# ADA4817.net
KiCad netlist of a schematic drawn in Altium Designer
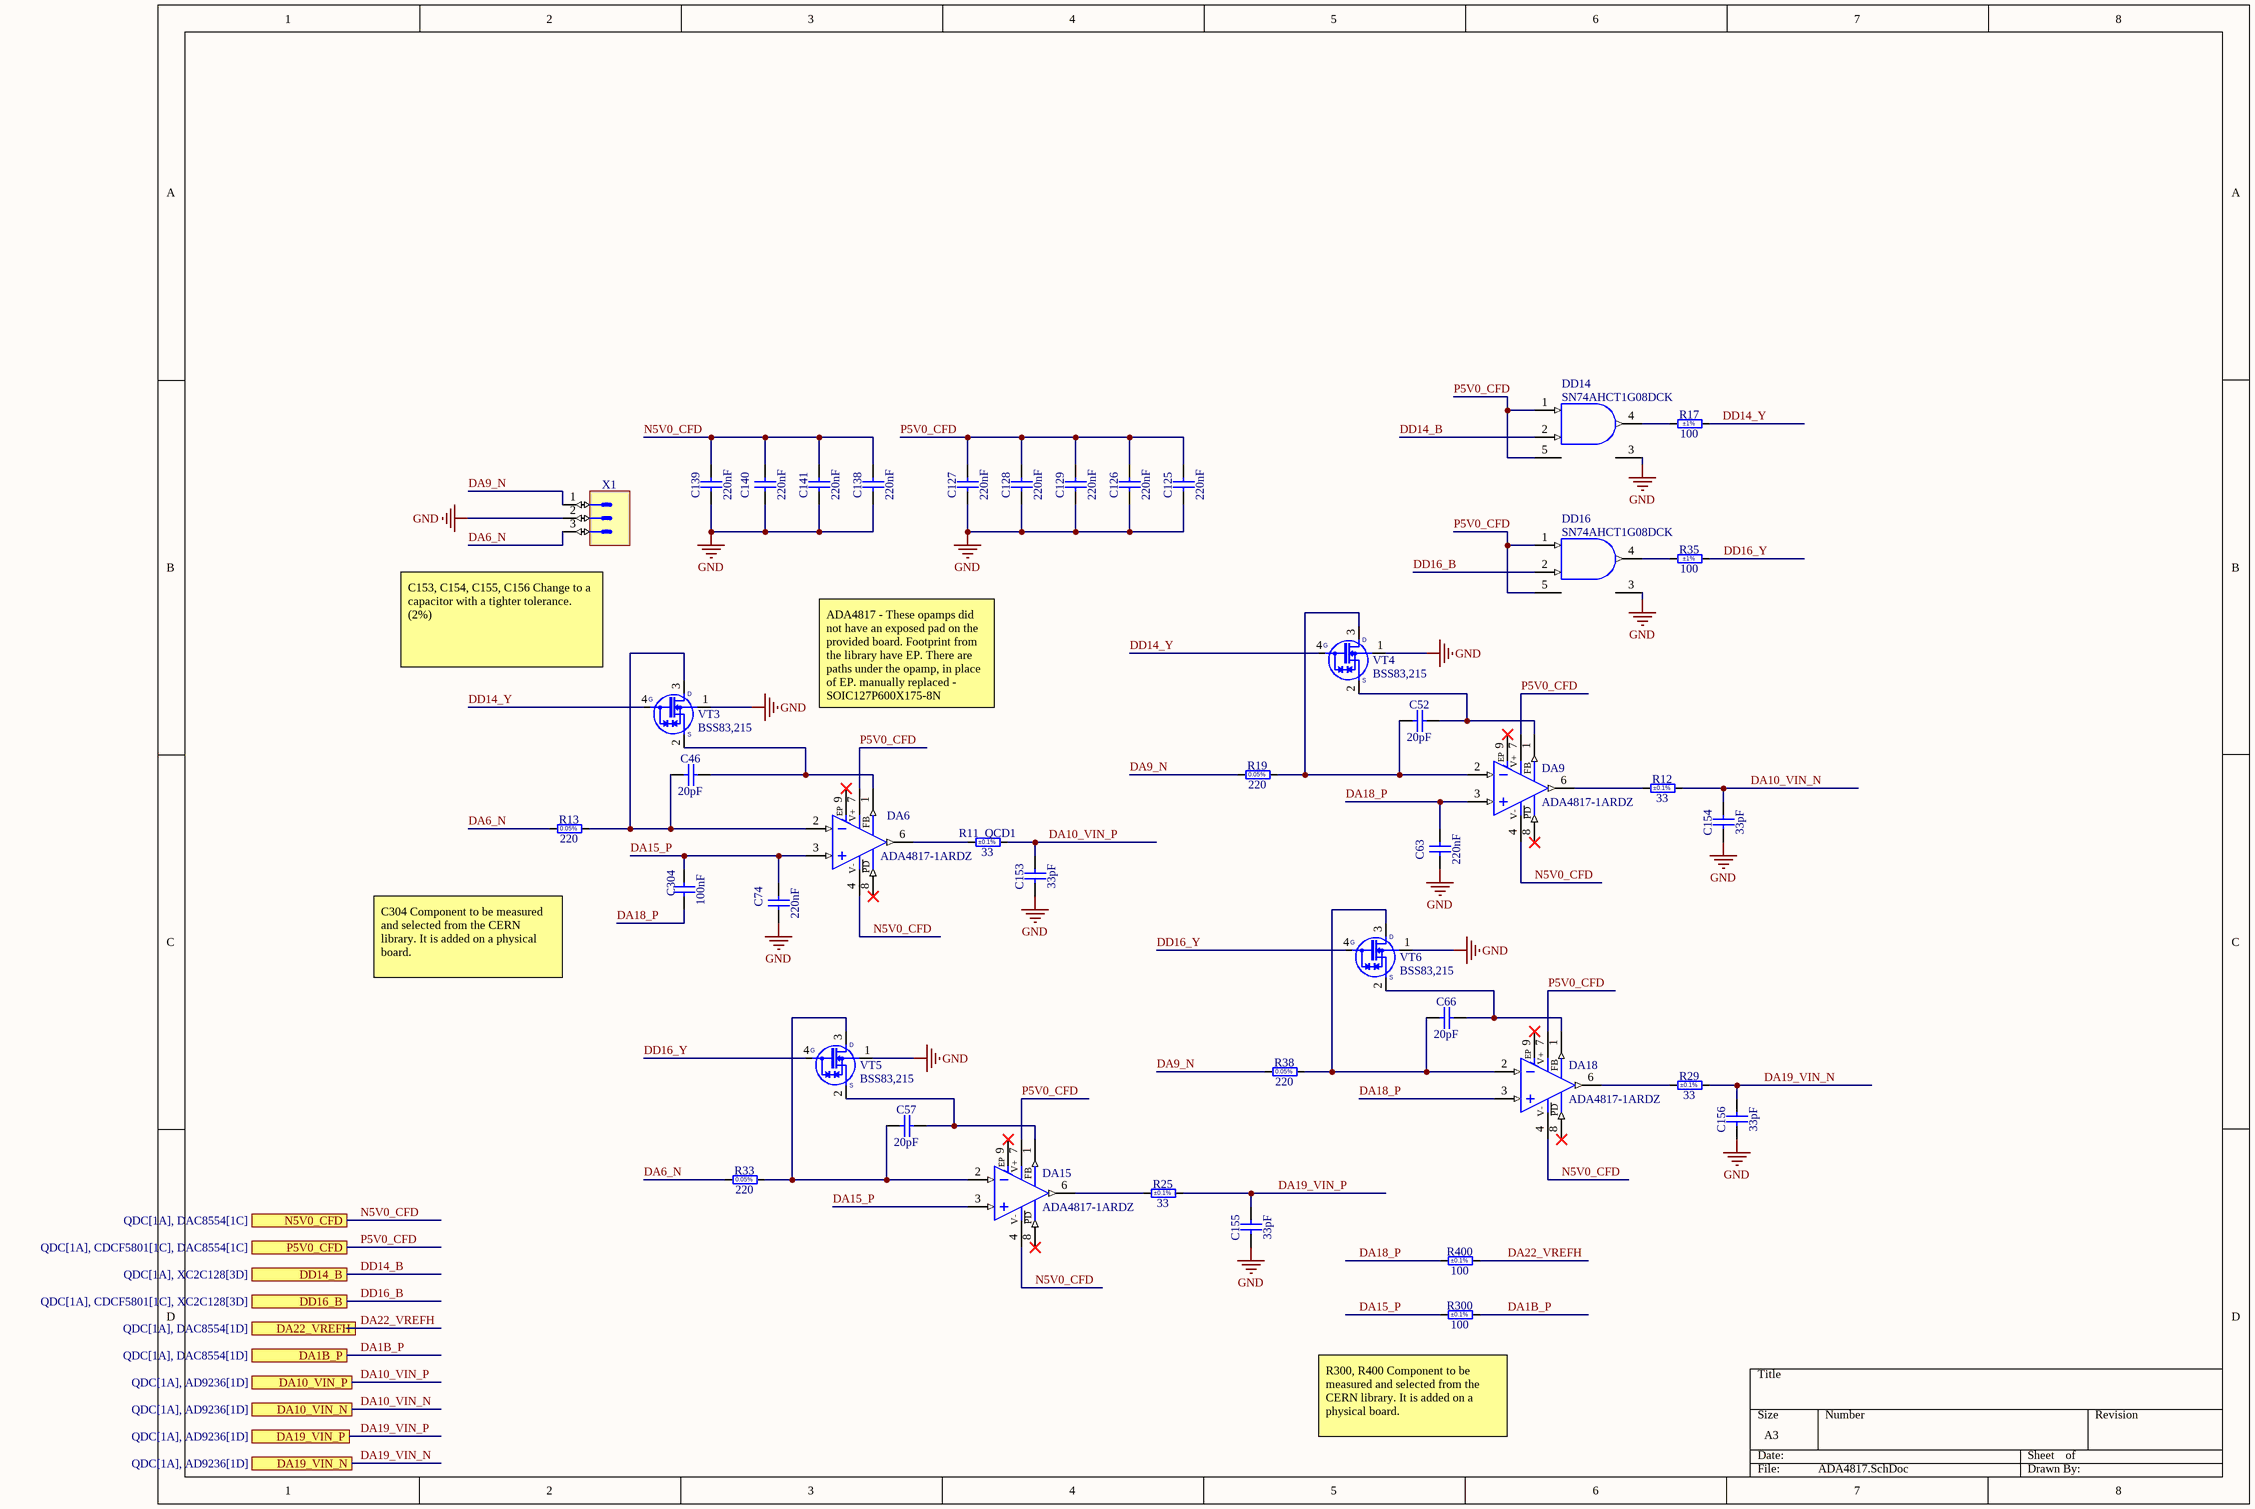
[diagram p0: ADA4817.SchDoc]

(export (version "E")
  (design (tool "Eeschema 10.0.6"))
  (components
    (comp (ref "C46")
      (value "20pF")
      (footprint "CAPC2012X135N")
      (description "Non-polarised capacitor")
      (fields
        (field (name "PART NUMBER") "CC0805_20PF_50V_2%_C0G")
        (field (name "VOLTAGE") "50V")
        (field (name "AUTHOR") "CERN DEM HF")
      )
      (libsource (lib "Capacitors") (part "Capacitor - non polarized"))
    )
    (comp (ref "C52")
      (value "20pF")
      (footprint "CAPC2012X135N")
      (description "Non-polarised capacitor")
      (fields
        (field (name "PART NUMBER") "CC0805_20PF_50V_2%_C0G")
        (field (name "VOLTAGE") "50V")
        (field (name "AUTHOR") "CERN DEM HF")
      )
      (libsource (lib "Capacitors") (part "Capacitor - non polarized"))
    )
    (comp (ref "C57")
      (value "20pF")
      (footprint "CAPC2012X135N")
      (description "Non-polarised capacitor")
      (fields
        (field (name "PART NUMBER") "CC0805_20PF_50V_2%_C0G")
        (field (name "VOLTAGE") "50V")
        (field (name "AUTHOR") "CERN DEM HF")
      )
      (libsource (lib "Capacitors") (part "Capacitor - non polarized"))
    )
    (comp (ref "C63")
      (value "220nF")
      (footprint "CAPC2012X135N")
      (description "Non-polarised capacitor")
      (fields
        (field (name "PART NUMBER") "CC0805_220NF_50V_10%_X7R")
        (field (name "VOLTAGE") "50V")
        (field (name "AUTHOR") "CERN DEM JLC")
      )
      (libsource (lib "Capacitors") (part "Capacitor - non polarized"))
    )
    (comp (ref "C66")
      (value "20pF")
      (footprint "CAPC2012X135N")
      (description "Non-polarised capacitor")
      (fields
        (field (name "PART NUMBER") "CC0805_20PF_50V_2%_C0G")
        (field (name "VOLTAGE") "50V")
        (field (name "AUTHOR") "CERN DEM HF")
      )
      (libsource (lib "Capacitors") (part "Capacitor - non polarized"))
    )
    (comp (ref "C74")
      (value "220nF")
      (footprint "CAPC2012X135N")
      (description "Non-polarised capacitor")
      (fields
        (field (name "PART NUMBER") "CC0805_220NF_50V_10%_X7R")
        (field (name "VOLTAGE") "50V")
        (field (name "AUTHOR") "CERN DEM JLC")
      )
      (libsource (lib "Capacitors") (part "Capacitor - non polarized"))
    )
    (comp (ref "C125")
      (value "220nF")
      (footprint "CAPC2012X135N")
      (description "Non-polarised capacitor")
      (fields
        (field (name "PART NUMBER") "CC0805_220NF_50V_10%_X7R")
        (field (name "VOLTAGE") "50V")
        (field (name "AUTHOR") "CERN DEM JLC")
      )
      (libsource (lib "Capacitors") (part "Capacitor - non polarized"))
    )
    (comp (ref "C126")
      (value "220nF")
      (footprint "CAPC2012X135N")
      (description "Non-polarised capacitor")
      (fields
        (field (name "PART NUMBER") "CC0805_220NF_50V_10%_X7R")
        (field (name "VOLTAGE") "50V")
        (field (name "AUTHOR") "CERN DEM JLC")
      )
      (libsource (lib "Capacitors") (part "Capacitor - non polarized"))
    )
    (comp (ref "C127")
      (value "220nF")
      (footprint "CAPC2012X135N")
      (description "Non-polarised capacitor")
      (fields
        (field (name "PART NUMBER") "CC0805_220NF_50V_10%_X7R")
        (field (name "VOLTAGE") "50V")
        (field (name "AUTHOR") "CERN DEM JLC")
      )
      (libsource (lib "Capacitors") (part "Capacitor - non polarized"))
    )
    (comp (ref "C128")
      (value "220nF")
      (footprint "CAPC2012X135N")
      (description "Non-polarised capacitor")
      (fields
        (field (name "PART NUMBER") "CC0805_220NF_50V_10%_X7R")
        (field (name "VOLTAGE") "50V")
        (field (name "AUTHOR") "CERN DEM JLC")
      )
      (libsource (lib "Capacitors") (part "Capacitor - non polarized"))
    )
    (comp (ref "C129")
      (value "220nF")
      (footprint "CAPC2012X135N")
      (description "Non-polarised capacitor")
      (fields
        (field (name "PART NUMBER") "CC0805_220NF_50V_10%_X7R")
        (field (name "VOLTAGE") "50V")
        (field (name "AUTHOR") "CERN DEM JLC")
      )
      (libsource (lib "Capacitors") (part "Capacitor - non polarized"))
    )
    (comp (ref "C138")
      (value "220nF")
      (footprint "CAPC2012X135N")
      (description "Non-polarised capacitor")
      (fields
        (field (name "PART NUMBER") "CC0805_220NF_50V_10%_X7R")
        (field (name "VOLTAGE") "50V")
        (field (name "AUTHOR") "CERN DEM JLC")
      )
      (libsource (lib "Capacitors") (part "Capacitor - non polarized"))
    )
    (comp (ref "C139")
      (value "220nF")
      (footprint "CAPC2012X135N")
      (description "Non-polarised capacitor")
      (fields
        (field (name "PART NUMBER") "CC0805_220NF_50V_10%_X7R")
        (field (name "VOLTAGE") "50V")
        (field (name "AUTHOR") "CERN DEM JLC")
      )
      (libsource (lib "Capacitors") (part "Capacitor - non polarized"))
    )
    (comp (ref "C140")
      (value "220nF")
      (footprint "CAPC2012X135N")
      (description "Non-polarised capacitor")
      (fields
        (field (name "PART NUMBER") "CC0805_220NF_50V_10%_X7R")
        (field (name "VOLTAGE") "50V")
        (field (name "AUTHOR") "CERN DEM JLC")
      )
      (libsource (lib "Capacitors") (part "Capacitor - non polarized"))
    )
    (comp (ref "C141")
      (value "220nF")
      (footprint "CAPC2012X135N")
      (description "Non-polarised capacitor")
      (fields
        (field (name "PART NUMBER") "CC0805_220NF_50V_10%_X7R")
        (field (name "VOLTAGE") "50V")
        (field (name "AUTHOR") "CERN DEM JLC")
      )
      (libsource (lib "Capacitors") (part "Capacitor - non polarized"))
    )
    (comp (ref "C153")
      (value "33pF")
      (footprint "CAPC1608X87N")
      (description "Non-polarised capacitor")
      (fields
        (field (name "PART NUMBER") "CC0603_33PF_50V_5%_NP0")
        (field (name "VOLTAGE") "50V")
        (field (name "AUTHOR") "CERN DEM JLC")
      )
      (libsource (lib "Capacitors") (part "Capacitor - non polarized"))
    )
    (comp (ref "C154")
      (value "33pF")
      (footprint "CAPC1608X87N")
      (description "Non-polarised capacitor")
      (fields
        (field (name "PART NUMBER") "CC0603_33PF_50V_5%_NP0")
        (field (name "VOLTAGE") "50V")
        (field (name "AUTHOR") "CERN DEM JLC")
      )
      (libsource (lib "Capacitors") (part "Capacitor - non polarized"))
    )
    (comp (ref "C155")
      (value "33pF")
      (footprint "CAPC1608X87N")
      (description "Non-polarised capacitor")
      (fields
        (field (name "PART NUMBER") "CC0603_33PF_50V_5%_NP0")
        (field (name "VOLTAGE") "50V")
        (field (name "AUTHOR") "CERN DEM JLC")
      )
      (libsource (lib "Capacitors") (part "Capacitor - non polarized"))
    )
    (comp (ref "C156")
      (value "33pF")
      (footprint "CAPC1608X87N")
      (description "Non-polarised capacitor")
      (fields
        (field (name "PART NUMBER") "CC0603_33PF_50V_5%_NP0")
        (field (name "VOLTAGE") "50V")
        (field (name "AUTHOR") "CERN DEM JLC")
      )
      (libsource (lib "Capacitors") (part "Capacitor - non polarized"))
    )
    (comp (ref "C304")
      (value "100nF")
      (footprint "CAPC2012X88N")
      (description "Non-polarised capacitor")
      (fields
        (field (name "PART NUMBER") "CC0805_100NF_50V_1%_NP0")
        (field (name "VOLTAGE") "50V")
        (field (name "AUTHOR") "CERN DEM HF")
      )
      (libsource (lib "Capacitors") (part "Capacitor - non polarized"))
    )
    (comp (ref "DA6")
      (value "ADA4817-1ARDZ")
      (footprint "SOIC127P600X175-8N")
      (description "Low Noise, 1GHz FastFEET Operational Amplifier")
      (fields
        (field (name "MANUFACTURER") "ANALOG DEVICES")
        (field (name "MANUFACTURER PART NUMBER") "ADA4817-1ARD")
        (field (name "AUTHOR") "CERN DEM JLC")
      )
      (libsource (lib "ICs And Semiconductors") (part "ADA4817-1ARDZ"))
    )
    (comp (ref "DA9")
      (value "ADA4817-1ARDZ")
      (footprint "SOIC127P600X175-8N")
      (description "Low Noise, 1GHz FastFEET Operational Amplifier")
      (fields
        (field (name "MANUFACTURER") "ANALOG DEVICES")
        (field (name "MANUFACTURER PART NUMBER") "ADA4817-1ARD")
        (field (name "AUTHOR") "CERN DEM JLC")
      )
      (libsource (lib "ICs And Semiconductors") (part "ADA4817-1ARDZ"))
    )
    (comp (ref "DA15")
      (value "ADA4817-1ARDZ")
      (footprint "SOIC127P600X175-8N")
      (description "Low Noise, 1GHz FastFEET Operational Amplifier")
      (fields
        (field (name "MANUFACTURER") "ANALOG DEVICES")
        (field (name "MANUFACTURER PART NUMBER") "ADA4817-1ARD")
        (field (name "AUTHOR") "CERN DEM JLC")
      )
      (libsource (lib "ICs And Semiconductors") (part "ADA4817-1ARDZ"))
    )
    (comp (ref "DA18")
      (value "ADA4817-1ARDZ")
      (footprint "SOIC127P600X175-8N")
      (description "Low Noise, 1GHz FastFEET Operational Amplifier")
      (fields
        (field (name "MANUFACTURER") "ANALOG DEVICES")
        (field (name "MANUFACTURER PART NUMBER") "ADA4817-1ARD")
        (field (name "AUTHOR") "CERN DEM JLC")
      )
      (libsource (lib "ICs And Semiconductors") (part "ADA4817-1ARDZ"))
    )
    (comp (ref "DD14")
      (value "SN74AHCT1G08DCK")
      (footprint "SOT65P210X110-5N")
      (description "Single 2-Input AND Gate")
      (fields (field (name "MANUFACTURER") "TEXAS INSTRUMENTS") (field (name "AUTHOR") "CERN DEM HF"))
      (libsource (lib "ICs And Semiconductors") (part "741G08"))
    )
    (comp (ref "DD16")
      (value "SN74AHCT1G08DCK")
      (footprint "SOT65P210X110-5N")
      (description "Single 2-Input AND Gate")
      (fields (field (name "MANUFACTURER") "TEXAS INSTRUMENTS") (field (name "AUTHOR") "CERN DEM HF"))
      (libsource (lib "ICs And Semiconductors") (part "741G08"))
    )
    (comp (ref "R11_QCD1")
      (value "33")
      (footprint "RESC1608X64N")
      (description "Resistor - 0.1%")
      (fields
        (field (name "TOLERANCE") "±0.1%")
        (field (name "PART NUMBER") "R0603_33R_0.1%_0.1W_10PPM")
        (field (name "POWER") "0.1W")
        (field (name "AUTHOR") "CERN DEM HF")
      )
      (libsource (lib "Resistors") (part "Resistor - 0.1%"))
    )
    (comp (ref "R12")
      (value "33")
      (footprint "RESC1608X64N")
      (description "Resistor - 0.1%")
      (fields
        (field (name "TOLERANCE") "±0.1%")
        (field (name "PART NUMBER") "R0603_33R_0.1%_0.1W_10PPM")
        (field (name "POWER") "0.1W")
        (field (name "AUTHOR") "CERN DEM HF")
      )
      (libsource (lib "Resistors") (part "Resistor - 0.1%"))
    )
    (comp (ref "R13")
      (value "220")
      (footprint "RESC2012X60N")
      (description "Resistor - 0.05%")
      (fields
        (field (name "PART NUMBER") "R0805_220R_0.05%_0.125W_10PPM")
        (field (name "POWER") "0.125W")
        (field (name "AUTHOR") "CERN DEM HF")
      )
      (libsource (lib "Resistors") (part "Resistor - 0.05%"))
    )
    (comp (ref "R17")
      (value "100")
      (footprint "RESC1608X55N")
      (description "Resistor - 1%")
      (fields
        (field (name "TOLERANCE") "±1%")
        (field (name "PART NUMBER") "R0603_100R_1%_0.1W_100PPM")
        (field (name "POWER") "0.1W")
        (field (name "AUTHOR") "CERN DEM JLC")
      )
      (libsource (lib "Resistors") (part "Resistor - 1%"))
    )
    (comp (ref "R19")
      (value "220")
      (footprint "RESC2012X60N")
      (description "Resistor - 0.05%")
      (fields
        (field (name "PART NUMBER") "R0805_220R_0.05%_0.125W_10PPM")
        (field (name "POWER") "0.125W")
        (field (name "AUTHOR") "CERN DEM HF")
      )
      (libsource (lib "Resistors") (part "Resistor - 0.05%"))
    )
    (comp (ref "R25")
      (value "33")
      (footprint "RESC1608X64N")
      (description "Resistor - 0.1%")
      (fields
        (field (name "TOLERANCE") "±0.1%")
        (field (name "PART NUMBER") "R0603_33R_0.1%_0.1W_10PPM")
        (field (name "POWER") "0.1W")
        (field (name "AUTHOR") "CERN DEM HF")
      )
      (libsource (lib "Resistors") (part "Resistor - 0.1%"))
    )
    (comp (ref "R29")
      (value "33")
      (footprint "RESC1608X64N")
      (description "Resistor - 0.1%")
      (fields
        (field (name "TOLERANCE") "±0.1%")
        (field (name "PART NUMBER") "R0603_33R_0.1%_0.1W_10PPM")
        (field (name "POWER") "0.1W")
        (field (name "AUTHOR") "CERN DEM HF")
      )
      (libsource (lib "Resistors") (part "Resistor - 0.1%"))
    )
    (comp (ref "R33")
      (value "220")
      (footprint "RESC2012X60N")
      (description "Resistor - 0.05%")
      (fields
        (field (name "PART NUMBER") "R0805_220R_0.05%_0.125W_10PPM")
        (field (name "POWER") "0.125W")
        (field (name "AUTHOR") "CERN DEM HF")
      )
      (libsource (lib "Resistors") (part "Resistor - 0.05%"))
    )
    (comp (ref "R35")
      (value "100")
      (footprint "RESC1608X55N")
      (description "Resistor - 1%")
      (fields
        (field (name "TOLERANCE") "±1%")
        (field (name "PART NUMBER") "R0603_100R_1%_0.1W_100PPM")
        (field (name "POWER") "0.1W")
        (field (name "AUTHOR") "CERN DEM JLC")
      )
      (libsource (lib "Resistors") (part "Resistor - 1%"))
    )
    (comp (ref "R38")
      (value "220")
      (footprint "RESC2012X60N")
      (description "Resistor - 0.05%")
      (fields
        (field (name "PART NUMBER") "R0805_220R_0.05%_0.125W_10PPM")
        (field (name "POWER") "0.125W")
        (field (name "AUTHOR") "CERN DEM HF")
      )
      (libsource (lib "Resistors") (part "Resistor - 0.05%"))
    )
    (comp (ref "R300")
      (value "100")
      (footprint "RES_VISHAY_FCHP0402")
      (description "Resistor - 0.1%")
      (fields
        (field (name "TOLERANCE") "±0.1%")
        (field (name "PART NUMBER") "R0402_100R_0.1%_1W_25PPM_VISHAY_FCHP0402E1000BS")
        (field (name "POWER") "1W")
        (field (name "AUTHOR") "CERN DEM HF")
      )
      (libsource (lib "Resistors") (part "Resistor - 0.1%"))
    )
    (comp (ref "R400")
      (value "100")
      (footprint "RES_VISHAY_FCHP0402")
      (description "Resistor - 0.1%")
      (fields
        (field (name "TOLERANCE") "±0.1%")
        (field (name "PART NUMBER") "R0402_100R_0.1%_1W_25PPM_VISHAY_FCHP0402E1000BS")
        (field (name "POWER") "1W")
        (field (name "AUTHOR") "CERN DEM HF")
      )
      (libsource (lib "Resistors") (part "Resistor - 0.1%"))
    )
    (comp (ref "VT3")
      (value "BSS83,215")
      (footprint "SOT143N")
      (description "10V, 50 mA N-Channel Enhancement Switching Transistor")
      (fields (field (name "MANUFACTURER") "NXP SEMICONDUCTORS") (field (name "AUTHOR") "CERN DEM JLC"))
      (libsource (lib "ICs And Semiconductors") (part "BSS83"))
    )
    (comp (ref "VT4")
      (value "BSS83,215")
      (footprint "SOT143N")
      (description "10V, 50 mA N-Channel Enhancement Switching Transistor")
      (fields (field (name "MANUFACTURER") "NXP SEMICONDUCTORS") (field (name "AUTHOR") "CERN DEM JLC"))
      (libsource (lib "ICs And Semiconductors") (part "BSS83"))
    )
    (comp (ref "VT5")
      (value "BSS83,215")
      (footprint "SOT143N")
      (description "10V, 50 mA N-Channel Enhancement Switching Transistor")
      (fields (field (name "MANUFACTURER") "NXP SEMICONDUCTORS") (field (name "AUTHOR") "CERN DEM JLC"))
      (libsource (lib "ICs And Semiconductors") (part "BSS83"))
    )
    (comp (ref "VT6")
      (value "BSS83,215")
      (footprint "SOT143N")
      (description "10V, 50 mA N-Channel Enhancement Switching Transistor")
      (fields (field (name "MANUFACTURER") "NXP SEMICONDUCTORS") (field (name "AUTHOR") "CERN DEM JLC"))
      (libsource (lib "ICs And Semiconductors") (part "BSS83"))
    )
    (comp (ref "X1")
      (value "Header 3")
      (footprint "SAMTEC_DW-03-09-L-S-470")
      (description "Connector 3 Male")
      (fields
        (field (name "PART NUMBER") "SAMTEC_DW-03-09-L-S-470")
        (field (name "MANUFACTURER") "SAMTEC")
        (field (name "AUTHOR") "CERN DEM HF")
      )
      (libsource (lib "Connectors") (part "Connector 3 Male"))
    )
  )
  (nets
    (net (code "1") (name "/DA1B_P") (class "Default")
      (node (ref "R300") (pin "2") (pinfunction "2_2") (pintype "passive"))
    )
    (net (code "2") (name "/DA6_N") (class "Default")
      (node (ref "R13") (pin "1") (pinfunction "1_1") (pintype "passive"))
      (node (ref "R33") (pin "1") (pinfunction "1_1") (pintype "passive"))
      (node (ref "X1") (pin "3") (pinfunction "3_3") (pintype "bidirectional"))
    )
    (net (code "3") (name "/DA9_N") (class "Default")
      (node (ref "R19") (pin "1") (pinfunction "1_1") (pintype "passive"))
      (node (ref "R38") (pin "1") (pinfunction "1_1") (pintype "passive"))
      (node (ref "X1") (pin "1") (pinfunction "1_1") (pintype "bidirectional"))
    )
    (net (code "4") (name "/DA10_VIN_N") (class "Default")
      (node (ref "C154") (pin "2") (pinfunction "2_2") (pintype "passive"))
      (node (ref "R12") (pin "2") (pinfunction "2_2") (pintype "passive"))
    )
    (net (code "5") (name "/DA10_VIN_P") (class "Default")
      (node (ref "C153") (pin "2") (pinfunction "2_2") (pintype "passive"))
      (node (ref "R11_QCD1") (pin "2") (pinfunction "2_2") (pintype "passive"))
    )
    (net (code "6") (name "/DA15_P") (class "Default")
      (node (ref "C304") (pin "2") (pinfunction "2_2") (pintype "passive"))
      (node (ref "C74") (pin "2") (pinfunction "2_2") (pintype "passive"))
      (node (ref "DA15") (pin "3") (pinfunction "IN+_3") (pintype "input"))
      (node (ref "DA6") (pin "3") (pinfunction "IN+_3") (pintype "input"))
      (node (ref "R300") (pin "1") (pinfunction "1_1") (pintype "passive"))
    )
    (net (code "7") (name "/DA18_P") (class "Default")
      (node (ref "C304") (pin "1") (pinfunction "1_1") (pintype "passive"))
      (node (ref "C63") (pin "2") (pinfunction "2_2") (pintype "passive"))
      (node (ref "DA18") (pin "3") (pinfunction "IN+_3") (pintype "input"))
      (node (ref "DA9") (pin "3") (pinfunction "IN+_3") (pintype "input"))
      (node (ref "R400") (pin "1") (pinfunction "1_1") (pintype "passive"))
    )
    (net (code "8") (name "/DA19_VIN_N") (class "Default")
      (node (ref "C156") (pin "2") (pinfunction "2_2") (pintype "passive"))
      (node (ref "R29") (pin "2") (pinfunction "2_2") (pintype "passive"))
    )
    (net (code "9") (name "/DA19_VIN_P") (class "Default")
      (node (ref "C155") (pin "2") (pinfunction "2_2") (pintype "passive"))
      (node (ref "R25") (pin "2") (pinfunction "2_2") (pintype "passive"))
    )
    (net (code "10") (name "/DA22_VREFH") (class "Default")
      (node (ref "R400") (pin "2") (pinfunction "2_2") (pintype "passive"))
    )
    (net (code "11") (name "/DD14_B") (class "Default")
      (node (ref "DD14") (pin "2") (pinfunction "A_2") (pintype "input"))
    )
    (net (code "12") (name "/DD14_Y") (class "Default")
      (node (ref "R17") (pin "2") (pinfunction "2_2") (pintype "passive"))
      (node (ref "VT3") (pin "4") (pinfunction "G_4") (pintype "passive"))
      (node (ref "VT4") (pin "4") (pinfunction "G_4") (pintype "passive"))
    )
    (net (code "13") (name "/DD16_B") (class "Default")
      (node (ref "DD16") (pin "2") (pinfunction "A_2") (pintype "input"))
    )
    (net (code "14") (name "/DD16_Y") (class "Default")
      (node (ref "R35") (pin "2") (pinfunction "2_2") (pintype "passive"))
      (node (ref "VT5") (pin "4") (pinfunction "G_4") (pintype "passive"))
      (node (ref "VT6") (pin "4") (pinfunction "G_4") (pintype "passive"))
    )
    (net (code "15") (name "/N5V0_CFD") (class "Default")
      (node (ref "C138") (pin "2") (pinfunction "2_2") (pintype "passive"))
      (node (ref "C139") (pin "2") (pinfunction "2_2") (pintype "passive"))
      (node (ref "C140") (pin "2") (pinfunction "2_2") (pintype "passive"))
      (node (ref "C141") (pin "2") (pinfunction "2_2") (pintype "passive"))
      (node (ref "DA15") (pin "4") (pinfunction "-Vs_4") (pintype "power_in"))
      (node (ref "DA18") (pin "4") (pinfunction "-Vs_4") (pintype "power_in"))
      (node (ref "DA6") (pin "4") (pinfunction "-Vs_4") (pintype "power_in"))
      (node (ref "DA9") (pin "4") (pinfunction "-Vs_4") (pintype "power_in"))
    )
    (net (code "16") (name "/P5V0_CFD") (class "Default")
      (node (ref "C125") (pin "2") (pinfunction "2_2") (pintype "passive"))
      (node (ref "C126") (pin "2") (pinfunction "2_2") (pintype "passive"))
      (node (ref "C127") (pin "2") (pinfunction "2_2") (pintype "passive"))
      (node (ref "C128") (pin "2") (pinfunction "2_2") (pintype "passive"))
      (node (ref "C129") (pin "2") (pinfunction "2_2") (pintype "passive"))
      (node (ref "DA15") (pin "7") (pinfunction "+Vs_7") (pintype "power_in"))
      (node (ref "DA18") (pin "7") (pinfunction "+Vs_7") (pintype "power_in"))
      (node (ref "DA6") (pin "7") (pinfunction "+Vs_7") (pintype "power_in"))
      (node (ref "DA9") (pin "7") (pinfunction "+Vs_7") (pintype "power_in"))
      (node (ref "DD14") (pin "1") (pinfunction "B_1") (pintype "input"))
      (node (ref "DD14") (pin "5") (pinfunction "VCC_5") (pintype "power_in"))
      (node (ref "DD16") (pin "1") (pinfunction "B_1") (pintype "input"))
      (node (ref "DD16") (pin "5") (pinfunction "VCC_5") (pintype "power_in"))
    )
    (net (code "17") (name "GND") (class "Default")
      (node (ref "C125") (pin "1") (pinfunction "1_1") (pintype "passive"))
      (node (ref "C126") (pin "1") (pinfunction "1_1") (pintype "passive"))
      (node (ref "C127") (pin "1") (pinfunction "1_1") (pintype "passive"))
      (node (ref "C128") (pin "1") (pinfunction "1_1") (pintype "passive"))
      (node (ref "C129") (pin "1") (pinfunction "1_1") (pintype "passive"))
      (node (ref "C138") (pin "1") (pinfunction "1_1") (pintype "passive"))
      (node (ref "C139") (pin "1") (pinfunction "1_1") (pintype "passive"))
      (node (ref "C140") (pin "1") (pinfunction "1_1") (pintype "passive"))
      (node (ref "C141") (pin "1") (pinfunction "1_1") (pintype "passive"))
      (node (ref "C153") (pin "1") (pinfunction "1_1") (pintype "passive"))
      (node (ref "C154") (pin "1") (pinfunction "1_1") (pintype "passive"))
      (node (ref "C155") (pin "1") (pinfunction "1_1") (pintype "passive"))
      (node (ref "C156") (pin "1") (pinfunction "1_1") (pintype "passive"))
      (node (ref "C63") (pin "1") (pinfunction "1_1") (pintype "passive"))
      (node (ref "C74") (pin "1") (pinfunction "1_1") (pintype "passive"))
      (node (ref "DD14") (pin "3") (pinfunction "GND_3") (pintype "power_in"))
      (node (ref "DD16") (pin "3") (pinfunction "GND_3") (pintype "power_in"))
      (node (ref "VT3") (pin "1") (pinfunction "SUB_1") (pintype "passive"))
      (node (ref "VT4") (pin "1") (pinfunction "SUB_1") (pintype "passive"))
      (node (ref "VT5") (pin "1") (pinfunction "SUB_1") (pintype "passive"))
      (node (ref "VT6") (pin "1") (pinfunction "SUB_1") (pintype "passive"))
      (node (ref "X1") (pin "2") (pinfunction "2_2") (pintype "bidirectional"))
    )
    (net (code "18") (name "Net-(DA6-FB)") (class "Default")
      (node (ref "C46") (pin "2") (pinfunction "2_2") (pintype "passive"))
      (node (ref "DA6") (pin "1") (pinfunction "FB_1") (pintype "output"))
      (node (ref "VT3") (pin "2") (pinfunction "S_2") (pintype "passive"))
    )
    (net (code "19") (name "Net-(DA6-IN-)") (class "Default")
      (node (ref "C46") (pin "1") (pinfunction "1_1") (pintype "passive"))
      (node (ref "DA6") (pin "2") (pinfunction "IN-_2") (pintype "input"))
      (node (ref "R13") (pin "2") (pinfunction "2_2") (pintype "passive"))
      (node (ref "VT3") (pin "3") (pinfunction "D_3") (pintype "passive"))
    )
    (net (code "20") (name "Net-(DA6-OUT)") (class "Default")
      (node (ref "DA6") (pin "6") (pinfunction "OUT_6") (pintype "output"))
      (node (ref "R11_QCD1") (pin "1") (pinfunction "1_1") (pintype "passive"))
    )
    (net (code "21") (name "Net-(DA9-FB)") (class "Default")
      (node (ref "C52") (pin "2") (pinfunction "2_2") (pintype "passive"))
      (node (ref "DA9") (pin "1") (pinfunction "FB_1") (pintype "output"))
      (node (ref "VT4") (pin "2") (pinfunction "S_2") (pintype "passive"))
    )
    (net (code "22") (name "Net-(DA9-IN-)") (class "Default")
      (node (ref "C52") (pin "1") (pinfunction "1_1") (pintype "passive"))
      (node (ref "DA9") (pin "2") (pinfunction "IN-_2") (pintype "input"))
      (node (ref "R19") (pin "2") (pinfunction "2_2") (pintype "passive"))
      (node (ref "VT4") (pin "3") (pinfunction "D_3") (pintype "passive"))
    )
    (net (code "23") (name "Net-(DA9-OUT)") (class "Default")
      (node (ref "DA9") (pin "6") (pinfunction "OUT_6") (pintype "output"))
      (node (ref "R12") (pin "1") (pinfunction "1_1") (pintype "passive"))
    )
    (net (code "24") (name "Net-(DA15-FB)") (class "Default")
      (node (ref "C57") (pin "2") (pinfunction "2_2") (pintype "passive"))
      (node (ref "DA15") (pin "1") (pinfunction "FB_1") (pintype "output"))
      (node (ref "VT5") (pin "2") (pinfunction "S_2") (pintype "passive"))
    )
    (net (code "25") (name "Net-(DA15-IN-)") (class "Default")
      (node (ref "C57") (pin "1") (pinfunction "1_1") (pintype "passive"))
      (node (ref "DA15") (pin "2") (pinfunction "IN-_2") (pintype "input"))
      (node (ref "R33") (pin "2") (pinfunction "2_2") (pintype "passive"))
      (node (ref "VT5") (pin "3") (pinfunction "D_3") (pintype "passive"))
    )
    (net (code "26") (name "Net-(DA15-OUT)") (class "Default")
      (node (ref "DA15") (pin "6") (pinfunction "OUT_6") (pintype "output"))
      (node (ref "R25") (pin "1") (pinfunction "1_1") (pintype "passive"))
    )
    (net (code "27") (name "Net-(DA18-FB)") (class "Default")
      (node (ref "C66") (pin "2") (pinfunction "2_2") (pintype "passive"))
      (node (ref "DA18") (pin "1") (pinfunction "FB_1") (pintype "output"))
      (node (ref "VT6") (pin "2") (pinfunction "S_2") (pintype "passive"))
    )
    (net (code "28") (name "Net-(DA18-IN-)") (class "Default")
      (node (ref "C66") (pin "1") (pinfunction "1_1") (pintype "passive"))
      (node (ref "DA18") (pin "2") (pinfunction "IN-_2") (pintype "input"))
      (node (ref "R38") (pin "2") (pinfunction "2_2") (pintype "passive"))
      (node (ref "VT6") (pin "3") (pinfunction "D_3") (pintype "passive"))
    )
    (net (code "29") (name "Net-(DA18-OUT)") (class "Default")
      (node (ref "DA18") (pin "6") (pinfunction "OUT_6") (pintype "output"))
      (node (ref "R29") (pin "1") (pinfunction "1_1") (pintype "passive"))
    )
    (net (code "30") (name "Net-(DD14-Y)") (class "Default")
      (node (ref "DD14") (pin "4") (pinfunction "Y_4") (pintype "output"))
      (node (ref "R17") (pin "1") (pinfunction "1_1") (pintype "passive"))
    )
    (net (code "31") (name "Net-(DD16-Y)") (class "Default")
      (node (ref "DD16") (pin "4") (pinfunction "Y_4") (pintype "output"))
      (node (ref "R35") (pin "1") (pinfunction "1_1") (pintype "passive"))
    )
    (net (code "32") (name "unconnected-(DA6-EP-Pad9)") (class "Default")
      (node (ref "DA6") (pin "9") (pinfunction "EP_9") (pintype "power_in+no_connect"))
    )
    (net (code "33") (name "unconnected-(DA6-~{PD}-Pad8)") (class "Default")
      (node (ref "DA6") (pin "8") (pinfunction "~{PD}_8") (pintype "input+no_connect"))
    )
    (net (code "34") (name "unconnected-(DA9-EP-Pad9)") (class "Default")
      (node (ref "DA9") (pin "9") (pinfunction "EP_9") (pintype "power_in+no_connect"))
    )
    (net (code "35") (name "unconnected-(DA9-~{PD}-Pad8)") (class "Default")
      (node (ref "DA9") (pin "8") (pinfunction "~{PD}_8") (pintype "input+no_connect"))
    )
    (net (code "36") (name "unconnected-(DA15-EP-Pad9)") (class "Default")
      (node (ref "DA15") (pin "9") (pinfunction "EP_9") (pintype "power_in+no_connect"))
    )
    (net (code "37") (name "unconnected-(DA15-~{PD}-Pad8)") (class "Default")
      (node (ref "DA15") (pin "8") (pinfunction "~{PD}_8") (pintype "input+no_connect"))
    )
    (net (code "38") (name "unconnected-(DA18-EP-Pad9)") (class "Default")
      (node (ref "DA18") (pin "9") (pinfunction "EP_9") (pintype "power_in+no_connect"))
    )
    (net (code "39") (name "unconnected-(DA18-~{PD}-Pad8)") (class "Default")
      (node (ref "DA18") (pin "8") (pinfunction "~{PD}_8") (pintype "input+no_connect"))
    )
  )
)
